# MCLR.net
KiCad netlist of a schematic drawn in Altium Designer
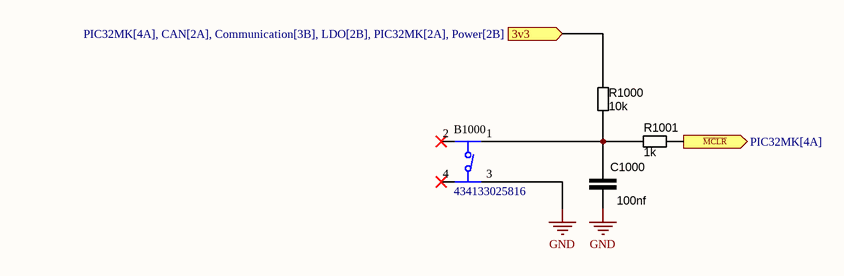
[diagram p0: MCLR.SchDoc]

(export (version "E")
  (design (tool "Eeschema 10.0.6"))
  (components
    (comp (ref "B1000")
      (value "434133025816")
      (footprint "434133025816")
      (fields (field (name "MF") "{'manufacturer': u'Wurth Electronics'}"))
      (libsource (lib "SnapEDA_Library2") (part "434133025816"))
    )
    (comp (ref "C1000")
      (value "100nf")
      (footprint "CAP_0603")
      (description "CAP CER 100nF 0603 25V X7R")
      (libsource (lib "CapacitorsIntegrated") (part "C000007"))
    )
    (comp (ref "R1000")
      (value "10k")
      (footprint "RES_0603")
      (description "RES 10K OHM 1% 1/10W 0603")
      (libsource (lib "ResistorsIntegrated") (part "R000006"))
    )
    (comp (ref "R1001")
      (value "1k")
      (footprint "RES_0603")
      (description "RES 1K OHM 1% 1/10W 0603")
      (libsource (lib "") (part "R000006_1"))
    )
  )
  (nets
    (net (code "1") (name "/3v3") (class "Default")
      (node (ref "R1000") (pin "2") (pinfunction "2_2") (pintype "passive"))
    )
    (net (code "2") (name "/~{MCLR}") (class "Default")
      (node (ref "R1001") (pin "1") (pinfunction "1_1") (pintype "passive"))
    )
    (net (code "3") (name "GND") (class "Default")
      (node (ref "B1000") (pin "3") (pinfunction "3_3") (pintype "passive"))
      (node (ref "C1000") (pin "1") (pinfunction "1_1") (pintype "passive"))
    )
    (net (code "4") (name "Net-(B1000-Pad1)") (class "Default")
      (node (ref "B1000") (pin "1") (pinfunction "1_1") (pintype "passive"))
      (node (ref "C1000") (pin "2") (pinfunction "2_2") (pintype "passive"))
      (node (ref "R1000") (pin "1") (pinfunction "1_1") (pintype "passive"))
      (node (ref "R1001") (pin "2") (pinfunction "2_2") (pintype "passive"))
    )
    (net (code "5") (name "unconnected-(B1000-Pad2)") (class "Default")
      (node (ref "B1000") (pin "2") (pinfunction "2_2") (pintype "passive+no_connect"))
    )
    (net (code "6") (name "unconnected-(B1000-Pad4)") (class "Default")
      (node (ref "B1000") (pin "4") (pinfunction "4_4") (pintype "passive+no_connect"))
    )
  )
)
